# big-module-shift.net
KiCad netlist of a schematic drawn in EAGLE
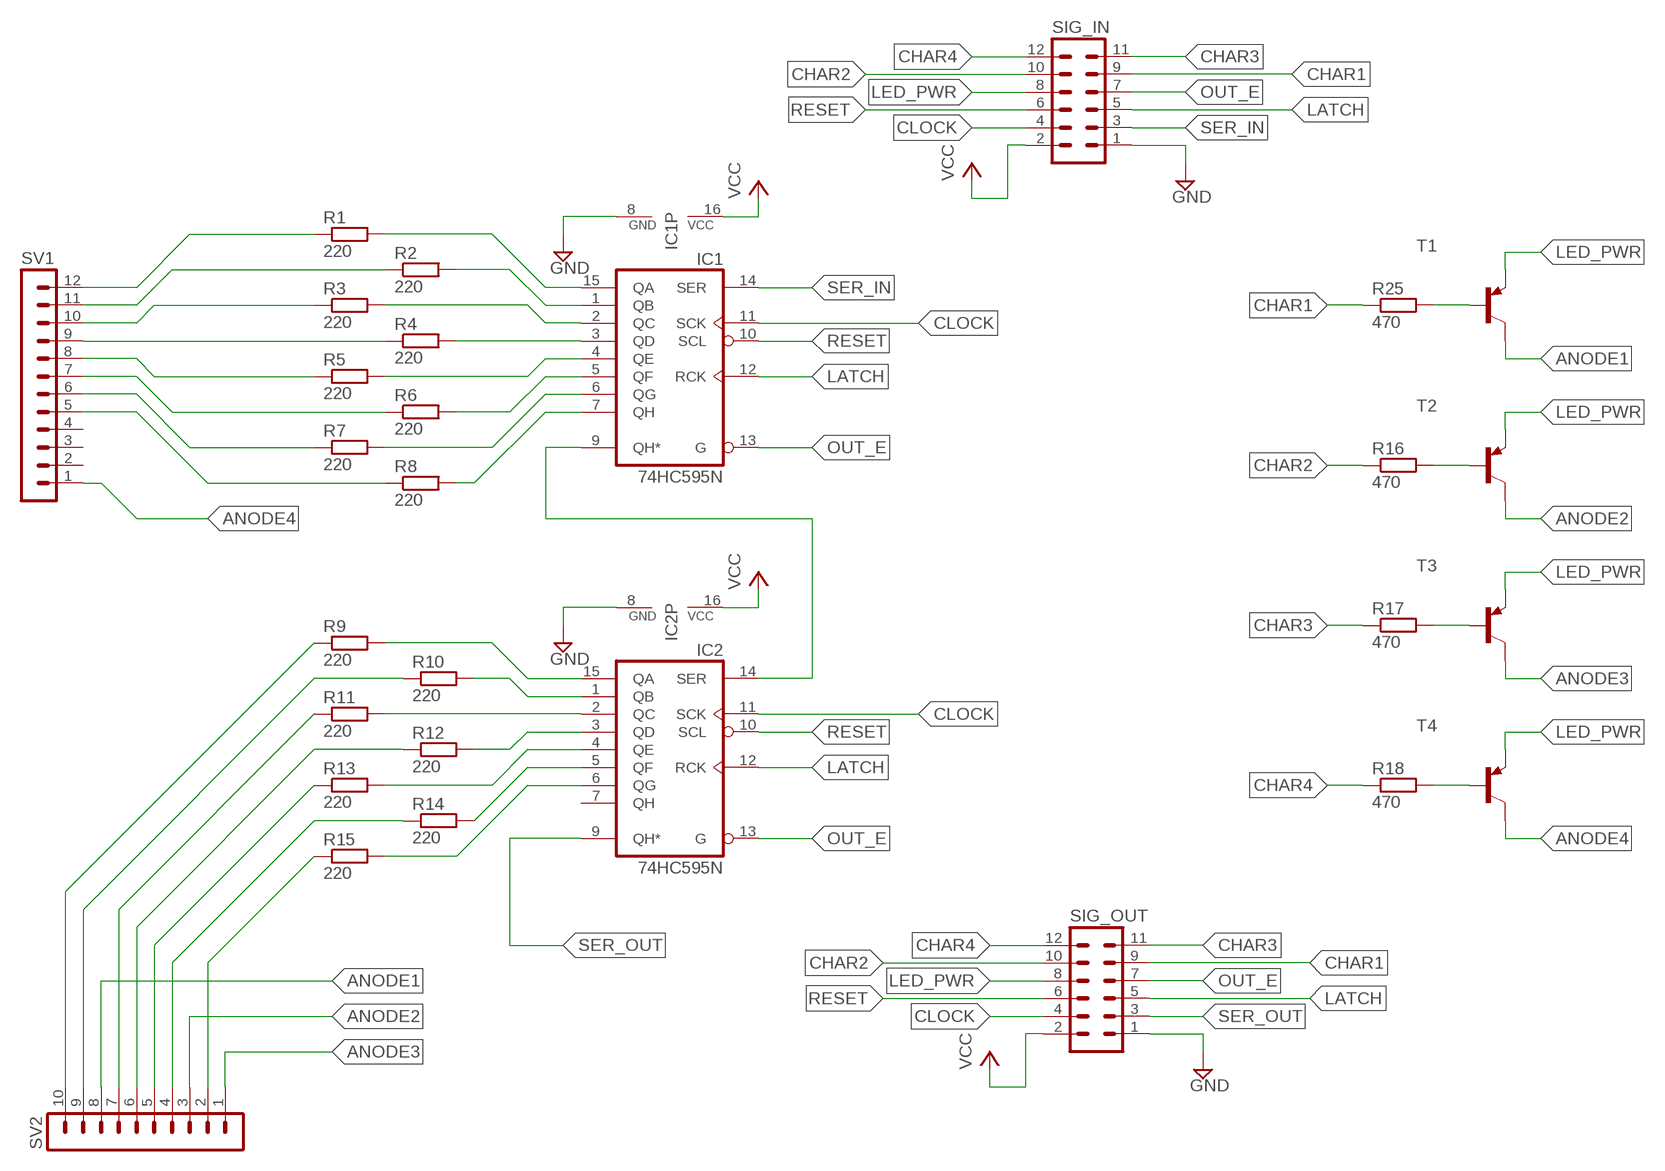
[diagram p0: schematic, sheet 1]

(export (version "E")
  (design (tool "Eeschema 10.0.6"))
  (components
    (comp (ref "IC1")
      (value "74HC595N")
      (footprint "eagle-import:DIL16")
      (libsource (lib "eagle-import") (part "74595NHC"))
    )
    (comp (ref "IC2")
      (value "74HC595N")
      (footprint "eagle-import:DIL16")
      (libsource (lib "eagle-import") (part "74595NHC"))
    )
    (comp (ref "R1")
      (value "220")
      (footprint "eagle-import:M0805")
      (libsource (lib "eagle-import") (part "resistor_R-EU_M0805"))
    )
    (comp (ref "R2")
      (value "220")
      (footprint "eagle-import:M0805")
      (libsource (lib "eagle-import") (part "resistor_R-EU_M0805"))
    )
    (comp (ref "R3")
      (value "220")
      (footprint "eagle-import:M0805")
      (libsource (lib "eagle-import") (part "resistor_R-EU_M0805"))
    )
    (comp (ref "R4")
      (value "220")
      (footprint "eagle-import:M0805")
      (libsource (lib "eagle-import") (part "resistor_R-EU_M0805"))
    )
    (comp (ref "R5")
      (value "220")
      (footprint "eagle-import:M0805")
      (libsource (lib "eagle-import") (part "resistor_R-EU_M0805"))
    )
    (comp (ref "R6")
      (value "220")
      (footprint "eagle-import:M0805")
      (libsource (lib "eagle-import") (part "resistor_R-EU_M0805"))
    )
    (comp (ref "R7")
      (value "220")
      (footprint "eagle-import:M0805")
      (libsource (lib "eagle-import") (part "resistor_R-EU_M0805"))
    )
    (comp (ref "R8")
      (value "220")
      (footprint "eagle-import:M0805")
      (libsource (lib "eagle-import") (part "resistor_R-EU_M0805"))
    )
    (comp (ref "R9")
      (value "220")
      (footprint "eagle-import:M0805")
      (libsource (lib "eagle-import") (part "resistor_R-EU_M0805"))
    )
    (comp (ref "R10")
      (value "220")
      (footprint "eagle-import:M0805")
      (libsource (lib "eagle-import") (part "resistor_R-EU_M0805"))
    )
    (comp (ref "R11")
      (value "220")
      (footprint "eagle-import:M0805")
      (libsource (lib "eagle-import") (part "resistor_R-EU_M0805"))
    )
    (comp (ref "R12")
      (value "220")
      (footprint "eagle-import:M0805")
      (libsource (lib "eagle-import") (part "resistor_R-EU_M0805"))
    )
    (comp (ref "R13")
      (value "220")
      (footprint "eagle-import:M0805")
      (libsource (lib "eagle-import") (part "resistor_R-EU_M0805"))
    )
    (comp (ref "R14")
      (value "220")
      (footprint "eagle-import:M0805")
      (libsource (lib "eagle-import") (part "resistor_R-EU_M0805"))
    )
    (comp (ref "R15")
      (value "220")
      (footprint "eagle-import:M0805")
      (libsource (lib "eagle-import") (part "resistor_R-EU_M0805"))
    )
    (comp (ref "R16")
      (value "470")
      (footprint "eagle-import:R0805")
      (libsource (lib "eagle-import") (part "R-EU_R0805"))
    )
    (comp (ref "R17")
      (value "470")
      (footprint "eagle-import:R0805")
      (libsource (lib "eagle-import") (part "R-EU_R0805"))
    )
    (comp (ref "R18")
      (value "470")
      (footprint "eagle-import:R0805")
      (libsource (lib "eagle-import") (part "R-EU_R0805"))
    )
    (comp (ref "R25")
      (value "470")
      (footprint "eagle-import:R0805")
      (libsource (lib "eagle-import") (part "R-EU_R0805"))
    )
    (comp (ref "SIG_IN")
      (value "MA06-2")
      (footprint "eagle-import:MA06-2")
      (libsource (lib "eagle-import") (part "MA06-2"))
    )
    (comp (ref "SIG_OUT")
      (value "MA06-2")
      (footprint "eagle-import:MA06-2")
      (libsource (lib "eagle-import") (part "MA06-2"))
    )
    (comp (ref "SV1")
      (value "MA12-1")
      (footprint "eagle-import:MA12-1")
      (libsource (lib "eagle-import") (part "MA12-1"))
    )
    (comp (ref "SV2")
      (value "MA10-1")
      (footprint "eagle-import:MA10-1")
      (libsource (lib "eagle-import") (part "MA10-1"))
    )
    (comp (ref "T1")
      (value "BC557B-PNP-TO92-EBC")
      (footprint "eagle-import:TO92-EBC")
      (libsource (lib "eagle-import") (part "-PNP-TO92-EBCBC557B"))
    )
    (comp (ref "T2")
      (value "BC557B-PNP-TO92-EBC")
      (footprint "eagle-import:TO92-EBC")
      (libsource (lib "eagle-import") (part "-PNP-TO92-EBCBC557B"))
    )
    (comp (ref "T3")
      (value "BC557B-PNP-TO92-EBC")
      (footprint "eagle-import:TO92-EBC")
      (libsource (lib "eagle-import") (part "-PNP-TO92-EBCBC557B"))
    )
    (comp (ref "T4")
      (value "BC557B-PNP-TO92-EBC")
      (footprint "eagle-import:TO92-EBC")
      (libsource (lib "eagle-import") (part "-PNP-TO92-EBCBC557B"))
    )
  )
  (nets
    (net (code "1") (name "ANODE1") (class "Default")
      (node (ref "SV2") (pin "8") (pinfunction "8_8") (pintype "passive"))
      (node (ref "T1") (pin "C") (pinfunction "C_C") (pintype "passive"))
    )
    (net (code "2") (name "ANODE2") (class "Default")
      (node (ref "SV2") (pin "3") (pinfunction "3_3") (pintype "passive"))
      (node (ref "T2") (pin "C") (pinfunction "C_C") (pintype "passive"))
    )
    (net (code "3") (name "ANODE3") (class "Default")
      (node (ref "SV2") (pin "1") (pinfunction "1_1") (pintype "passive"))
      (node (ref "T3") (pin "C") (pinfunction "C_C") (pintype "passive"))
    )
    (net (code "4") (name "ANODE4") (class "Default")
      (node (ref "SV1") (pin "1") (pinfunction "1_1") (pintype "passive"))
      (node (ref "T4") (pin "C") (pinfunction "C_C") (pintype "passive"))
    )
    (net (code "5") (name "CHAR1") (class "Default")
      (node (ref "R25") (pin "1") (pinfunction "1_1") (pintype "passive"))
      (node (ref "SIG_IN") (pin "9") (pinfunction "9_9") (pintype "passive"))
      (node (ref "SIG_OUT") (pin "9") (pinfunction "9_9") (pintype "passive"))
    )
    (net (code "6") (name "CHAR2") (class "Default")
      (node (ref "R16") (pin "1") (pinfunction "1_1") (pintype "passive"))
      (node (ref "SIG_IN") (pin "10") (pinfunction "10_10") (pintype "passive"))
      (node (ref "SIG_OUT") (pin "10") (pinfunction "10_10") (pintype "passive"))
    )
    (net (code "7") (name "CHAR3") (class "Default")
      (node (ref "R17") (pin "1") (pinfunction "1_1") (pintype "passive"))
      (node (ref "SIG_IN") (pin "11") (pinfunction "11_11") (pintype "passive"))
      (node (ref "SIG_OUT") (pin "11") (pinfunction "11_11") (pintype "passive"))
    )
    (net (code "8") (name "CHAR4") (class "Default")
      (node (ref "R18") (pin "1") (pinfunction "1_1") (pintype "passive"))
      (node (ref "SIG_IN") (pin "12") (pinfunction "12_12") (pintype "passive"))
      (node (ref "SIG_OUT") (pin "12") (pinfunction "12_12") (pintype "passive"))
    )
    (net (code "9") (name "CLOCK") (class "Default")
      (node (ref "IC1") (pin "11") (pinfunction "SCK_11") (pintype "input"))
      (node (ref "IC2") (pin "11") (pinfunction "SCK_11") (pintype "input"))
      (node (ref "SIG_IN") (pin "4") (pinfunction "4_4") (pintype "passive"))
      (node (ref "SIG_OUT") (pin "4") (pinfunction "4_4") (pintype "passive"))
    )
    (net (code "10") (name "GND") (class "Default")
      (node (ref "IC1") (pin "8") (pinfunction "GND_8") (pintype "power_in"))
      (node (ref "IC2") (pin "8") (pinfunction "GND_8") (pintype "power_in"))
      (node (ref "SIG_IN") (pin "1") (pinfunction "1_1") (pintype "passive"))
      (node (ref "SIG_OUT") (pin "1") (pinfunction "1_1") (pintype "passive"))
    )
    (net (code "11") (name "LATCH") (class "Default")
      (node (ref "IC1") (pin "12") (pinfunction "RCK_12") (pintype "input"))
      (node (ref "IC2") (pin "12") (pinfunction "RCK_12") (pintype "input"))
      (node (ref "SIG_IN") (pin "5") (pinfunction "5_5") (pintype "passive"))
      (node (ref "SIG_OUT") (pin "5") (pinfunction "5_5") (pintype "passive"))
    )
    (net (code "12") (name "LED_PWR") (class "Default")
      (node (ref "SIG_IN") (pin "8") (pinfunction "8_8") (pintype "passive"))
      (node (ref "SIG_OUT") (pin "8") (pinfunction "8_8") (pintype "passive"))
      (node (ref "T1") (pin "E") (pinfunction "E_E") (pintype "passive"))
      (node (ref "T2") (pin "E") (pinfunction "E_E") (pintype "passive"))
      (node (ref "T3") (pin "E") (pinfunction "E_E") (pintype "passive"))
      (node (ref "T4") (pin "E") (pinfunction "E_E") (pintype "passive"))
    )
    (net (code "13") (name "Net-(IC1A-QA)") (class "Default")
      (node (ref "IC1") (pin "15") (pinfunction "QA_15") (pintype "tri_state"))
      (node (ref "R1") (pin "2") (pinfunction "2_2") (pintype "passive"))
    )
    (net (code "14") (name "Net-(IC1A-QB)") (class "Default")
      (node (ref "IC1") (pin "1") (pinfunction "QB_1") (pintype "tri_state"))
      (node (ref "R2") (pin "2") (pinfunction "2_2") (pintype "passive"))
    )
    (net (code "15") (name "Net-(IC1A-QC)") (class "Default")
      (node (ref "IC1") (pin "2") (pinfunction "QC_2") (pintype "tri_state"))
      (node (ref "R3") (pin "2") (pinfunction "2_2") (pintype "passive"))
    )
    (net (code "16") (name "Net-(IC1A-QD)") (class "Default")
      (node (ref "IC1") (pin "3") (pinfunction "QD_3") (pintype "tri_state"))
      (node (ref "R4") (pin "2") (pinfunction "2_2") (pintype "passive"))
    )
    (net (code "17") (name "Net-(IC1A-QE)") (class "Default")
      (node (ref "IC1") (pin "4") (pinfunction "QE_4") (pintype "tri_state"))
      (node (ref "R5") (pin "2") (pinfunction "2_2") (pintype "passive"))
    )
    (net (code "18") (name "Net-(IC1A-QF)") (class "Default")
      (node (ref "IC1") (pin "5") (pinfunction "QF_5") (pintype "tri_state"))
      (node (ref "R6") (pin "2") (pinfunction "2_2") (pintype "passive"))
    )
    (net (code "19") (name "Net-(IC1A-QG)") (class "Default")
      (node (ref "IC1") (pin "6") (pinfunction "QG_6") (pintype "tri_state"))
      (node (ref "R7") (pin "2") (pinfunction "2_2") (pintype "passive"))
    )
    (net (code "20") (name "Net-(IC1A-QH)") (class "Default")
      (node (ref "IC1") (pin "7") (pinfunction "QH_7") (pintype "tri_state"))
      (node (ref "R8") (pin "2") (pinfunction "2_2") (pintype "passive"))
    )
    (net (code "21") (name "Net-(IC1A-QH*)") (class "Default")
      (node (ref "IC1") (pin "9") (pinfunction "QH*_9") (pintype "tri_state"))
      (node (ref "IC2") (pin "14") (pinfunction "SER_14") (pintype "input"))
    )
    (net (code "22") (name "Net-(IC2A-QA)") (class "Default")
      (node (ref "IC2") (pin "15") (pinfunction "QA_15") (pintype "tri_state"))
      (node (ref "R9") (pin "2") (pinfunction "2_2") (pintype "passive"))
    )
    (net (code "23") (name "Net-(IC2A-QB)") (class "Default")
      (node (ref "IC2") (pin "1") (pinfunction "QB_1") (pintype "tri_state"))
      (node (ref "R10") (pin "2") (pinfunction "2_2") (pintype "passive"))
    )
    (net (code "24") (name "Net-(IC2A-QC)") (class "Default")
      (node (ref "IC2") (pin "2") (pinfunction "QC_2") (pintype "tri_state"))
      (node (ref "R11") (pin "2") (pinfunction "2_2") (pintype "passive"))
    )
    (net (code "25") (name "Net-(IC2A-QD)") (class "Default")
      (node (ref "IC2") (pin "3") (pinfunction "QD_3") (pintype "tri_state"))
      (node (ref "R12") (pin "2") (pinfunction "2_2") (pintype "passive"))
    )
    (net (code "26") (name "Net-(IC2A-QE)") (class "Default")
      (node (ref "IC2") (pin "4") (pinfunction "QE_4") (pintype "tri_state"))
      (node (ref "R13") (pin "2") (pinfunction "2_2") (pintype "passive"))
    )
    (net (code "27") (name "Net-(IC2A-QF)") (class "Default")
      (node (ref "IC2") (pin "5") (pinfunction "QF_5") (pintype "tri_state"))
      (node (ref "R14") (pin "2") (pinfunction "2_2") (pintype "passive"))
    )
    (net (code "28") (name "Net-(IC2A-QG)") (class "Default")
      (node (ref "IC2") (pin "6") (pinfunction "QG_6") (pintype "tri_state"))
      (node (ref "R15") (pin "2") (pinfunction "2_2") (pintype "passive"))
    )
    (net (code "29") (name "Net-(R1-Pad1)") (class "Default")
      (node (ref "R1") (pin "1") (pinfunction "1_1") (pintype "passive"))
      (node (ref "SV1") (pin "12") (pinfunction "12_12") (pintype "passive"))
    )
    (net (code "30") (name "Net-(R2-Pad1)") (class "Default")
      (node (ref "R2") (pin "1") (pinfunction "1_1") (pintype "passive"))
      (node (ref "SV1") (pin "11") (pinfunction "11_11") (pintype "passive"))
    )
    (net (code "31") (name "Net-(R3-Pad1)") (class "Default")
      (node (ref "R3") (pin "1") (pinfunction "1_1") (pintype "passive"))
      (node (ref "SV1") (pin "10") (pinfunction "10_10") (pintype "passive"))
    )
    (net (code "32") (name "Net-(R4-Pad1)") (class "Default")
      (node (ref "R4") (pin "1") (pinfunction "1_1") (pintype "passive"))
      (node (ref "SV1") (pin "9") (pinfunction "9_9") (pintype "passive"))
    )
    (net (code "33") (name "Net-(R5-Pad1)") (class "Default")
      (node (ref "R5") (pin "1") (pinfunction "1_1") (pintype "passive"))
      (node (ref "SV1") (pin "8") (pinfunction "8_8") (pintype "passive"))
    )
    (net (code "34") (name "Net-(R6-Pad1)") (class "Default")
      (node (ref "R6") (pin "1") (pinfunction "1_1") (pintype "passive"))
      (node (ref "SV1") (pin "7") (pinfunction "7_7") (pintype "passive"))
    )
    (net (code "35") (name "Net-(R7-Pad1)") (class "Default")
      (node (ref "R7") (pin "1") (pinfunction "1_1") (pintype "passive"))
      (node (ref "SV1") (pin "6") (pinfunction "6_6") (pintype "passive"))
    )
    (net (code "36") (name "Net-(R8-Pad1)") (class "Default")
      (node (ref "R8") (pin "1") (pinfunction "1_1") (pintype "passive"))
      (node (ref "SV1") (pin "5") (pinfunction "5_5") (pintype "passive"))
    )
    (net (code "37") (name "Net-(R9-Pad1)") (class "Default")
      (node (ref "R9") (pin "1") (pinfunction "1_1") (pintype "passive"))
      (node (ref "SV2") (pin "10") (pinfunction "10_10") (pintype "passive"))
    )
    (net (code "38") (name "Net-(R10-Pad1)") (class "Default")
      (node (ref "R10") (pin "1") (pinfunction "1_1") (pintype "passive"))
      (node (ref "SV2") (pin "9") (pinfunction "9_9") (pintype "passive"))
    )
    (net (code "39") (name "Net-(R11-Pad1)") (class "Default")
      (node (ref "R11") (pin "1") (pinfunction "1_1") (pintype "passive"))
      (node (ref "SV2") (pin "7") (pinfunction "7_7") (pintype "passive"))
    )
    (net (code "40") (name "Net-(R12-Pad1)") (class "Default")
      (node (ref "R12") (pin "1") (pinfunction "1_1") (pintype "passive"))
      (node (ref "SV2") (pin "6") (pinfunction "6_6") (pintype "passive"))
    )
    (net (code "41") (name "Net-(R13-Pad1)") (class "Default")
      (node (ref "R13") (pin "1") (pinfunction "1_1") (pintype "passive"))
      (node (ref "SV2") (pin "5") (pinfunction "5_5") (pintype "passive"))
    )
    (net (code "42") (name "Net-(R14-Pad1)") (class "Default")
      (node (ref "R14") (pin "1") (pinfunction "1_1") (pintype "passive"))
      (node (ref "SV2") (pin "4") (pinfunction "4_4") (pintype "passive"))
    )
    (net (code "43") (name "Net-(R15-Pad1)") (class "Default")
      (node (ref "R15") (pin "1") (pinfunction "1_1") (pintype "passive"))
      (node (ref "SV2") (pin "2") (pinfunction "2_2") (pintype "passive"))
    )
    (net (code "44") (name "Net-(R16-Pad2)") (class "Default")
      (node (ref "R16") (pin "2") (pinfunction "2_2") (pintype "passive"))
      (node (ref "T2") (pin "B") (pinfunction "B_B") (pintype "passive"))
    )
    (net (code "45") (name "Net-(R17-Pad2)") (class "Default")
      (node (ref "R17") (pin "2") (pinfunction "2_2") (pintype "passive"))
      (node (ref "T3") (pin "B") (pinfunction "B_B") (pintype "passive"))
    )
    (net (code "46") (name "Net-(R18-Pad2)") (class "Default")
      (node (ref "R18") (pin "2") (pinfunction "2_2") (pintype "passive"))
      (node (ref "T4") (pin "B") (pinfunction "B_B") (pintype "passive"))
    )
    (net (code "47") (name "Net-(R25-Pad2)") (class "Default")
      (node (ref "R25") (pin "2") (pinfunction "2_2") (pintype "passive"))
      (node (ref "T1") (pin "B") (pinfunction "B_B") (pintype "passive"))
    )
    (net (code "48") (name "OUT_E") (class "Default")
      (node (ref "IC1") (pin "13") (pinfunction "G_13") (pintype "input"))
      (node (ref "IC2") (pin "13") (pinfunction "G_13") (pintype "input"))
      (node (ref "SIG_IN") (pin "7") (pinfunction "7_7") (pintype "passive"))
      (node (ref "SIG_OUT") (pin "7") (pinfunction "7_7") (pintype "passive"))
    )
    (net (code "49") (name "RESET") (class "Default")
      (node (ref "IC1") (pin "10") (pinfunction "SCL_10") (pintype "input"))
      (node (ref "IC2") (pin "10") (pinfunction "SCL_10") (pintype "input"))
      (node (ref "SIG_IN") (pin "6") (pinfunction "6_6") (pintype "passive"))
      (node (ref "SIG_OUT") (pin "6") (pinfunction "6_6") (pintype "passive"))
    )
    (net (code "50") (name "SER_IN") (class "Default")
      (node (ref "IC1") (pin "14") (pinfunction "SER_14") (pintype "input"))
      (node (ref "SIG_IN") (pin "3") (pinfunction "3_3") (pintype "passive"))
    )
    (net (code "51") (name "SER_OUT") (class "Default")
      (node (ref "IC2") (pin "9") (pinfunction "QH*_9") (pintype "tri_state"))
      (node (ref "SIG_OUT") (pin "3") (pinfunction "3_3") (pintype "passive"))
    )
    (net (code "52") (name "VCC") (class "Default")
      (node (ref "IC1") (pin "16") (pinfunction "VCC_16") (pintype "power_in"))
      (node (ref "IC2") (pin "16") (pinfunction "VCC_16") (pintype "power_in"))
      (node (ref "SIG_IN") (pin "2") (pinfunction "2_2") (pintype "passive"))
      (node (ref "SIG_OUT") (pin "2") (pinfunction "2_2") (pintype "passive"))
    )
    (net (code "53") (name "unconnected-(IC2A-QH-Pad7)") (class "Default")
      (node (ref "IC2") (pin "7") (pinfunction "QH_7") (pintype "tri_state"))
    )
    (net (code "54") (name "unconnected-(SV1-Pad2)") (class "Default")
      (node (ref "SV1") (pin "2") (pinfunction "2_2") (pintype "passive"))
    )
    (net (code "55") (name "unconnected-(SV1-Pad3)") (class "Default")
      (node (ref "SV1") (pin "3") (pinfunction "3_3") (pintype "passive"))
    )
    (net (code "56") (name "unconnected-(SV1-Pad4)") (class "Default")
      (node (ref "SV1") (pin "4") (pinfunction "4_4") (pintype "passive"))
    )
  )
)
